# HVSUP_ISOL_Mainboard.net
KiCad netlist of a schematic drawn in Altium Designer
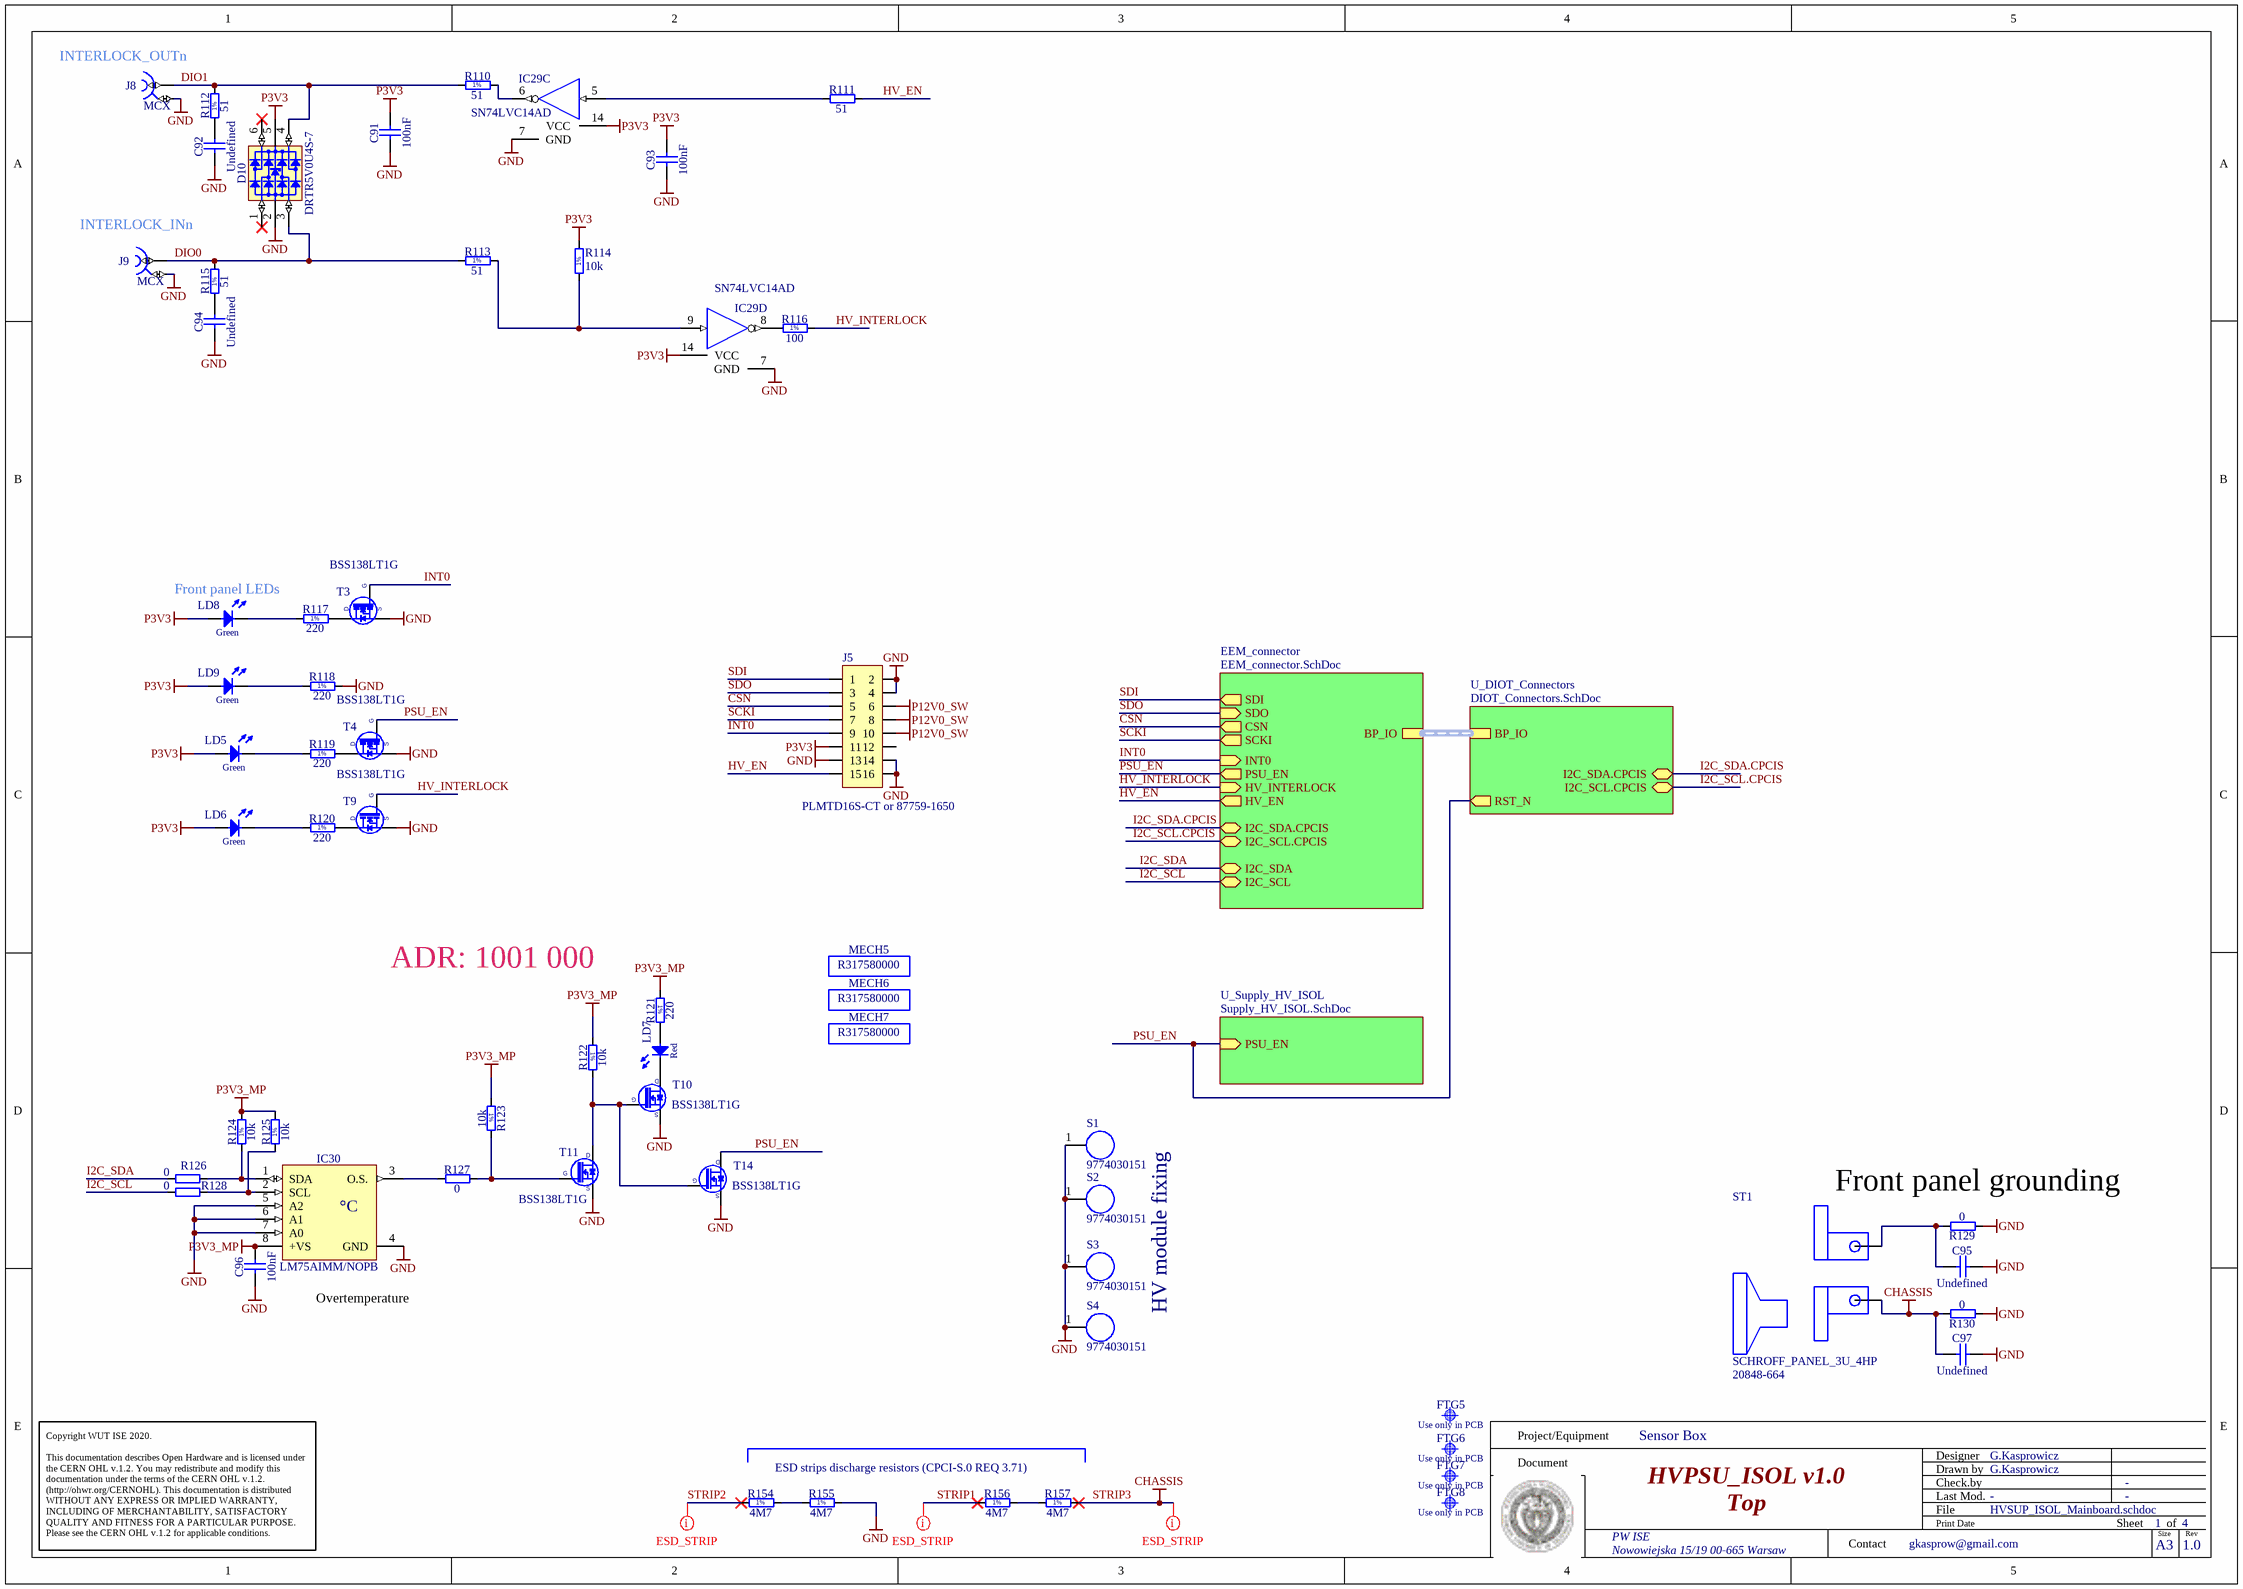
[diagram p0: HVSUP_ISOL_Mainboard.schdoc]

(export (version "E")
  (design (tool "Eeschema 10.0.6"))
  (components
    (comp (ref "C91")
      (value "100nF")
      (footprint "CAPC1005X55N")
      (description "Non-polarised capacitor")
      (fields
        (field (name "PART NUMBER") "CC0402_100NF_16V_10%_X7R")
        (field (name "VOLTAGE") "16V")
        (field (name "AUTHOR") "CERN DEM JLC")
      )
      (libsource (lib "Capacitors") (part "Capacitor - non polarized"))
    )
    (comp (ref "C92")
      (value "Undefined")
      (footprint "CAPC1608X90N")
      (description "Non-polarised capacitor")
      (fields (field (name "PART NUMBER") "CC0603_NO-VALUE") (field (name "AUTHOR") "CERN DEM MR"))
      (libsource (lib "Capacitors") (part "Capacitor - non polarized"))
    )
    (comp (ref "C93")
      (value "100nF")
      (footprint "CAPC1005X55N")
      (description "Non-polarised capacitor")
      (fields
        (field (name "PART NUMBER") "CC0402_100NF_16V_10%_X7R")
        (field (name "VOLTAGE") "16V")
        (field (name "AUTHOR") "CERN DEM JLC")
      )
      (libsource (lib "Capacitors") (part "Capacitor - non polarized"))
    )
    (comp (ref "C94")
      (value "Undefined")
      (footprint "CAPC1608X90N")
      (description "Non-polarised capacitor")
      (fields (field (name "PART NUMBER") "CC0603_NO-VALUE") (field (name "AUTHOR") "CERN DEM MR"))
      (libsource (lib "Capacitors") (part "Capacitor - non polarized"))
    )
    (comp (ref "C95")
      (value "Undefined")
      (footprint "CAPC2012X135N")
      (description "Non-polarised capacitor")
      (fields (field (name "PART NUMBER") "CC0805_NO-VALUE") (field (name "AUTHOR") "CERN DEM JLC"))
      (libsource (lib "Capacitors") (part "Capacitor - non polarized"))
    )
    (comp (ref "C96")
      (value "100nF")
      (footprint "CAPC1005X55N")
      (description "Non-polarised capacitor")
      (fields
        (field (name "PART NUMBER") "CC0402_100NF_16V_10%_X5R")
        (field (name "VOLTAGE") "16V")
        (field (name "AUTHOR") "CERN DEM JLC")
      )
      (libsource (lib "Capacitors") (part "Capacitor - non polarized"))
    )
    (comp (ref "C97")
      (value "Undefined")
      (footprint "CAPC2012X135N")
      (description "Non-polarised capacitor")
      (fields (field (name "PART NUMBER") "CC0805_NO-VALUE") (field (name "AUTHOR") "CERN DEM JLC"))
      (libsource (lib "Capacitors") (part "Capacitor - non polarized"))
    )
    (comp (ref "D10")
      (value "DRTR5V0U4S-7")
      (footprint "SOT65P210X110-6N")
      (description "Integrated Quad Ultra-Low Capacitance ESD Protection")
      (fields (field (name "MANUFACTURER") "DIODES") (field (name "AUTHOR") "GK"))
      (libsource (lib "Diodes") (part "D_TVS_DRTR5V0U4S-7"))
    )
    (comp (ref "FTG5")
      (value "Use only in PCB")
      (footprint "FIDUCIAL_TOP_C100-200")
      (description "Fiducial Target")
      (fields (field (name "PART NUMBER") "FIDUCIAL_TARGET_C100-200") (field (name "AUTHOR") "CERN DEM JLC"))
      (libsource (lib "Eletro-mechanical") (part "Fiducial Target"))
    )
    (comp (ref "FTG6")
      (value "Use only in PCB")
      (footprint "FIDUCIAL_TOP_S100-200")
      (description "Fiducial Target")
      (fields (field (name "PART NUMBER") "FIDUCIAL_TARGET_S100-200") (field (name "AUTHOR") "CERN DEM JLC"))
      (libsource (lib "Eletro-mechanical") (part "Fiducial Target"))
    )
    (comp (ref "FTG7")
      (value "Use only in PCB")
      (footprint "FIDUCIAL_TOP_S100-200")
      (description "Fiducial Target")
      (fields (field (name "PART NUMBER") "FIDUCIAL_TARGET_S100-200") (field (name "AUTHOR") "CERN DEM JLC"))
      (libsource (lib "Eletro-mechanical") (part "Fiducial Target"))
    )
    (comp (ref "FTG8")
      (value "Use only in PCB")
      (footprint "FIDUCIAL_TOP_S100-200")
      (description "Fiducial Target")
      (fields (field (name "PART NUMBER") "FIDUCIAL_TARGET_S100-200") (field (name "AUTHOR") "CERN DEM JLC"))
      (libsource (lib "Eletro-mechanical") (part "Fiducial Target"))
    )
    (comp (ref "IC29")
      (value "SN74LVC14AD")
      (footprint "SOIC127P600X175-14N")
      (description "Hex Schmitt-Trigger Inverter")
      (fields (field (name "MANUFACTURER") "TEXAS INSTRUMENTS") (field (name "AUTHOR") "CERN DEM JMW"))
      (libsource (lib "ICs And Semiconductors") (part "7414"))
    )
    (comp (ref "IC30")
      (value "LM75AIMM/NOPB")
      (footprint "SOP65P490X109-8N")
      (description "Digital Temperature Sensor and Thermal Watchdog with Two-Wire Interface")
      (fields (field (name "MANUFACTURER") "TEXAS INSTRUMENTS") (field (name "AUTHOR") "CERN DEM JLC"))
      (libsource (lib "ICs And Semiconductors") (part "LM75"))
    )
    (comp (ref "J5")
      (value "PLMTD16S-CT or 87759-1650")
      (footprint "87759-1650")
      (description "2mm  dual row rheader (Maritex)")
      (fields (field (name "MANUFACTURER") "Molex") (field (name "MANUFACTURER PART NUMBER") "87759-1650"))
      (libsource (lib "LIBRARY_SCH") (part "CON_2x8 2mm male"))
    )
    (comp (ref "J8")
      (value "MCX")
      (footprint "AMPHENOL_919-383J-51A")
      (fields
        (field (name "PART NUMBER") "AMPHENOL_919-383J-51A")
        (field (name "MANUFACTURER") "AMPHENOL")
        (field (name "MANUFACTURER PART NUMBER") "919-383J-51A")
        (field (name "AUTHOR") "CERN DEM BC")
      )
      (libsource (lib "Connectors") (part "Coax_1Female_1Shield"))
    )
    (comp (ref "J9")
      (value "MCX")
      (footprint "AMPHENOL_919-383J-51A")
      (fields
        (field (name "PART NUMBER") "AMPHENOL_919-383J-51A")
        (field (name "MANUFACTURER") "AMPHENOL")
        (field (name "MANUFACTURER PART NUMBER") "919-383J-51A")
        (field (name "AUTHOR") "CERN DEM BC")
      )
      (libsource (lib "Connectors") (part "Coax_1Female_1Shield"))
    )
    (comp (ref "LD5")
      (value "Green")
      (footprint "LED_DIALIGHT_555-230")
      (description "LED Green 1C 2A")
      (fields
        (field (name "PART NUMBER") "LED_DIALIGHT_555-2301F")
        (field (name "MANUFACTURER") "DIALIGHT")
        (field (name "AUTHOR") "CERN DEM JMW")
      )
      (libsource (lib "ICs And Semiconductors") (part "LED Green 1C 2A"))
    )
    (comp (ref "LD6")
      (value "Green")
      (footprint "LED_DIALIGHT_555-230")
      (description "LED Green 1C 2A")
      (fields
        (field (name "PART NUMBER") "LED_DIALIGHT_555-2301F")
        (field (name "MANUFACTURER") "DIALIGHT")
        (field (name "AUTHOR") "CERN DEM JMW")
      )
      (libsource (lib "ICs And Semiconductors") (part "LED Green 1C 2A"))
    )
    (comp (ref "LD7")
      (value "Red")
      (footprint "LED_DIALIGHT_555-200")
      (description "LED Red 1C 2A")
      (fields
        (field (name "PART NUMBER") "LED_DIALIGHT_555-2001F")
        (field (name "MANUFACTURER") "DIALIGHT")
        (field (name "AUTHOR") "CERN DEM JMW")
      )
      (libsource (lib "ICs And Semiconductors") (part "LED Red 1C 2A"))
    )
    (comp (ref "LD8")
      (value "Green")
      (footprint "LED_DIALIGHT_555-230")
      (description "LED Green 1C 2A")
      (fields
        (field (name "PART NUMBER") "LED_DIALIGHT_555-2301F")
        (field (name "MANUFACTURER") "DIALIGHT")
        (field (name "AUTHOR") "CERN DEM JMW")
      )
      (libsource (lib "ICs And Semiconductors") (part "LED Green 1C 2A"))
    )
    (comp (ref "LD9")
      (value "Green")
      (footprint "LED_DIALIGHT_555-230")
      (description "LED Green 1C 2A")
      (fields
        (field (name "PART NUMBER") "LED_DIALIGHT_555-2301F")
        (field (name "MANUFACTURER") "DIALIGHT")
        (field (name "AUTHOR") "CERN DEM JMW")
      )
      (libsource (lib "ICs And Semiconductors") (part "LED Green 1C 2A"))
    )
    (comp (ref "MECH5")
      (value "R317580000")
      (footprint "GENERIC_MECH")
      (description "SHV connector")
      (fields (field (name "MANUFACTURER") "Radiall") (field (name "AUTHOR") "GK"))
      (libsource (lib "Mechanical") (part "Generic_mechanical"))
    )
    (comp (ref "MECH6")
      (value "R317580000")
      (footprint "GENERIC_MECH")
      (description "SHV connector")
      (fields (field (name "MANUFACTURER") "Radiall") (field (name "AUTHOR") "GK"))
      (libsource (lib "Mechanical") (part "Generic_mechanical"))
    )
    (comp (ref "MECH7")
      (value "R317580000")
      (footprint "GENERIC_MECH")
      (description "SHV connector")
      (fields (field (name "MANUFACTURER") "Radiall") (field (name "AUTHOR") "GK"))
      (libsource (lib "Mechanical") (part "Generic_mechanical"))
    )
    (comp (ref "R110")
      (value "51")
      (footprint "RESC1005X40N")
      (description "Resistor - 1%")
      (fields
        (field (name "PART NUMBER") "R0402_51R_1%_0.0625W_100PPM")
        (field (name "POWER") "0.0625W")
        (field (name "AUTHOR") "CERN DEM JLC")
      )
      (libsource (lib "Resistors") (part "Resistor - 1%"))
    )
    (comp (ref "R111")
      (value "51")
      (footprint "RESC1005X40N")
      (description "Resistor - 1%")
      (fields
        (field (name "PART NUMBER") "R0402_51R_1%_0.0625W_100PPM")
        (field (name "POWER") "0.0625W")
        (field (name "AUTHOR") "CERN DEM JLC")
      )
      (libsource (lib "Resistors") (part "Resistor - 1%"))
    )
    (comp (ref "R112")
      (value "51")
      (footprint "RESC1005X40N")
      (description "Resistor - 1%")
      (fields
        (field (name "PART NUMBER") "R0402_51R_1%_0.0625W_100PPM")
        (field (name "POWER") "0.0625W")
        (field (name "AUTHOR") "CERN DEM JLC")
      )
      (libsource (lib "Resistors") (part "Resistor - 1%"))
    )
    (comp (ref "R113")
      (value "51")
      (footprint "RESC1005X40N")
      (description "Resistor - 1%")
      (fields
        (field (name "PART NUMBER") "R0402_51R_1%_0.0625W_100PPM")
        (field (name "POWER") "0.0625W")
        (field (name "AUTHOR") "CERN DEM JLC")
      )
      (libsource (lib "Resistors") (part "Resistor - 1%"))
    )
    (comp (ref "R114")
      (value "10k")
      (footprint "RESC1005X40N")
      (description "Resistor - 1%")
      (fields
        (field (name "PART NUMBER") "R0402_10K_1%_0.0625W_100PPM")
        (field (name "POWER") "0.0625W")
        (field (name "AUTHOR") "CERN DEM JLC")
      )
      (libsource (lib "Resistors") (part "Resistor - 1%"))
    )
    (comp (ref "R115")
      (value "51")
      (footprint "RESC1005X40N")
      (description "Resistor - 1%")
      (fields
        (field (name "PART NUMBER") "R0402_51R_1%_0.0625W_100PPM")
        (field (name "POWER") "0.0625W")
        (field (name "AUTHOR") "CERN DEM JLC")
      )
      (libsource (lib "Resistors") (part "Resistor - 1%"))
    )
    (comp (ref "R116")
      (value "100")
      (footprint "RESC1005X40N")
      (description "Resistor - 1%")
      (fields
        (field (name "PART NUMBER") "R0402_100R_1%_0.0625W_100PPM")
        (field (name "POWER") "0.0625W")
        (field (name "AUTHOR") "CERN DEM JLC")
      )
      (libsource (lib "Resistors") (part "Resistor - 1%"))
    )
    (comp (ref "R117")
      (value "220")
      (footprint "RESC1608X55N")
      (description "Resistor - 1%")
      (fields
        (field (name "PART NUMBER") "R0603_220R_1%_0.1W_100PPM")
        (field (name "POWER") "0.1W")
        (field (name "AUTHOR") "CERN DEM JLC")
      )
      (libsource (lib "Resistors") (part "Resistor - 1%"))
    )
    (comp (ref "R118")
      (value "220")
      (footprint "RESC1608X55N")
      (description "Resistor - 1%")
      (fields
        (field (name "PART NUMBER") "R0603_220R_1%_0.1W_100PPM")
        (field (name "POWER") "0.1W")
        (field (name "AUTHOR") "CERN DEM JLC")
      )
      (libsource (lib "Resistors") (part "Resistor - 1%"))
    )
    (comp (ref "R119")
      (value "220")
      (footprint "RESC1608X55N")
      (description "Resistor - 1%")
      (fields
        (field (name "PART NUMBER") "R0603_220R_1%_0.1W_100PPM")
        (field (name "POWER") "0.1W")
        (field (name "AUTHOR") "CERN DEM JLC")
      )
      (libsource (lib "Resistors") (part "Resistor - 1%"))
    )
    (comp (ref "R120")
      (value "220")
      (footprint "RESC1608X55N")
      (description "Resistor - 1%")
      (fields
        (field (name "PART NUMBER") "R0603_220R_1%_0.1W_100PPM")
        (field (name "POWER") "0.1W")
        (field (name "AUTHOR") "CERN DEM JLC")
      )
      (libsource (lib "Resistors") (part "Resistor - 1%"))
    )
    (comp (ref "R121")
      (value "220")
      (footprint "RESC1608X55N")
      (description "Resistor - 1%")
      (fields
        (field (name "PART NUMBER") "R0603_220R_1%_0.1W_100PPM")
        (field (name "POWER") "0.1W")
        (field (name "AUTHOR") "CERN DEM JLC")
      )
      (libsource (lib "Resistors") (part "Resistor - 1%"))
    )
    (comp (ref "R122")
      (value "10k")
      (footprint "RESC1005X40N")
      (description "Resistor - 1%")
      (fields
        (field (name "PART NUMBER") "R0402_10K_1%_0.0625W_100PPM")
        (field (name "POWER") "0.0625W")
        (field (name "AUTHOR") "CERN DEM JLC")
      )
      (libsource (lib "Resistors") (part "Resistor - 1%"))
    )
    (comp (ref "R123")
      (value "10k")
      (footprint "RESC1005X40N")
      (description "Resistor - 1%")
      (fields
        (field (name "PART NUMBER") "R0402_10K_1%_0.0625W_100PPM")
        (field (name "POWER") "0.0625W")
        (field (name "AUTHOR") "CERN DEM JLC")
      )
      (libsource (lib "Resistors") (part "Resistor - 1%"))
    )
    (comp (ref "R124")
      (value "10k")
      (footprint "RESC1005X40N")
      (description "Resistor - 1%")
      (fields
        (field (name "PART NUMBER") "R0402_10K_1%_0.0625W_100PPM")
        (field (name "POWER") "0.0625W")
        (field (name "AUTHOR") "CERN DEM JLC")
      )
      (libsource (lib "Resistors") (part "Resistor - 1%"))
    )
    (comp (ref "R125")
      (value "10k")
      (footprint "RESC1005X40N")
      (description "Resistor - 1%")
      (fields
        (field (name "PART NUMBER") "R0402_10K_1%_0.0625W_100PPM")
        (field (name "POWER") "0.0625W")
        (field (name "AUTHOR") "CERN DEM JLC")
      )
      (libsource (lib "Resistors") (part "Resistor - 1%"))
    )
    (comp (ref "R126")
      (value "0")
      (footprint "RESC1005X40N")
      (description "Resistor")
      (fields
        (field (name "PART NUMBER") "R0402_0R_JUMPER")
        (field (name "MANUFACTURER") "GENERIC")
        (field (name "AUTHOR") "CERN DEM JLC")
      )
      (libsource (lib "Resistors") (part "Resistor"))
    )
    (comp (ref "R127")
      (value "0")
      (footprint "RESC1005X40N")
      (description "Resistor")
      (fields
        (field (name "PART NUMBER") "R0402_0R_JUMPER")
        (field (name "MANUFACTURER") "GENERIC")
        (field (name "AUTHOR") "CERN DEM JLC")
      )
      (libsource (lib "Resistors") (part "Resistor"))
    )
    (comp (ref "R128")
      (value "0")
      (footprint "RESC1005X40N")
      (description "Resistor")
      (fields
        (field (name "PART NUMBER") "R0402_0R_JUMPER")
        (field (name "MANUFACTURER") "GENERIC")
        (field (name "AUTHOR") "CERN DEM JLC")
      )
      (libsource (lib "Resistors") (part "Resistor"))
    )
    (comp (ref "R129")
      (value "0")
      (footprint "RESC1608X55N")
      (description "Resistor")
      (fields
        (field (name "PART NUMBER") "R0603_0R_JUMPER")
        (field (name "MANUFACTURER") "GENERIC")
        (field (name "AUTHOR") "CERN DEM JLC")
      )
      (libsource (lib "Resistors") (part "Resistor"))
    )
    (comp (ref "R130")
      (value "0")
      (footprint "RESC1608X55N")
      (description "Resistor")
      (fields
        (field (name "PART NUMBER") "R0603_0R_JUMPER")
        (field (name "MANUFACTURER") "GENERIC")
        (field (name "AUTHOR") "CERN DEM JLC")
      )
      (libsource (lib "Resistors") (part "Resistor"))
    )
    (comp (ref "R154")
      (value "4M7")
      (footprint "RESC2113X55N")
      (description "Resistor - 1%")
      (fields
        (field (name "PART NUMBER") "R0805_4M7_1%_0.125W_100PPM_VISHAY_CRCW e3")
        (field (name "POWER") "0.125W")
        (field (name "AUTHOR") "CERN DEM BR")
      )
      (libsource (lib "Resistors") (part "Resistor - 1%"))
    )
    (comp (ref "R155")
      (value "4M7")
      (footprint "RESC2113X55N")
      (description "Resistor - 1%")
      (fields
        (field (name "PART NUMBER") "R0805_4M7_1%_0.125W_100PPM_VISHAY_CRCW e3")
        (field (name "POWER") "0.125W")
        (field (name "AUTHOR") "CERN DEM BR")
      )
      (libsource (lib "Resistors") (part "Resistor - 1%"))
    )
    (comp (ref "R156")
      (value "4M7")
      (footprint "RESC2113X55N")
      (description "Resistor - 1%")
      (fields
        (field (name "PART NUMBER") "R0805_4M7_1%_0.125W_100PPM_VISHAY_CRCW e3")
        (field (name "POWER") "0.125W")
        (field (name "AUTHOR") "CERN DEM BR")
      )
      (libsource (lib "Resistors") (part "Resistor - 1%"))
    )
    (comp (ref "R157")
      (value "4M7")
      (footprint "RESC2113X55N")
      (description "Resistor - 1%")
      (fields
        (field (name "PART NUMBER") "R0805_4M7_1%_0.125W_100PPM_VISHAY_CRCW e3")
        (field (name "POWER") "0.125W")
        (field (name "AUTHOR") "CERN DEM BR")
      )
      (libsource (lib "Resistors") (part "Resistor - 1%"))
    )
    (comp (ref "S1")
      (value "9774030151")
      (footprint "9774030151")
      (description "WA-SMSI SMD Steel Spacer with internal Thread")
      (fields (field (name "MANUFACTURER") "Wurth Elektronik") (field (name "CREATED BY") "Baojun Chen"))
      (libsource (lib "Altium_SMSI_SMT_STEEL_SPACER_M2_5_THREAD_INTERNAL_rev15a") (part "WA-SMSI,  9774030151"))
    )
    (comp (ref "S2")
      (value "9774030151")
      (footprint "9774030151")
      (description "WA-SMSI SMD Steel Spacer with internal Thread")
      (fields (field (name "MANUFACTURER") "Wurth Elektronik") (field (name "CREATED BY") "Baojun Chen"))
      (libsource (lib "Altium_SMSI_SMT_STEEL_SPACER_M2_5_THREAD_INTERNAL_rev15a") (part "WA-SMSI,  9774030151"))
    )
    (comp (ref "S3")
      (value "9774030151")
      (footprint "9774030151")
      (description "WA-SMSI SMD Steel Spacer with internal Thread")
      (fields (field (name "MANUFACTURER") "Wurth Elektronik") (field (name "CREATED BY") "Baojun Chen"))
      (libsource (lib "Altium_SMSI_SMT_STEEL_SPACER_M2_5_THREAD_INTERNAL_rev15a") (part "WA-SMSI,  9774030151"))
    )
    (comp (ref "S4")
      (value "9774030151")
      (footprint "9774030151")
      (description "WA-SMSI SMD Steel Spacer with internal Thread")
      (fields (field (name "MANUFACTURER") "Wurth Elektronik") (field (name "CREATED BY") "Baojun Chen"))
      (libsource (lib "Altium_SMSI_SMT_STEEL_SPACER_M2_5_THREAD_INTERNAL_rev15a") (part "WA-SMSI,  9774030151"))
    )
    (comp (ref "ST1")
      (value "SCHROFF_PANEL_3U_4HP")
      (footprint "SCHROFF_PANEL_3HP_4U")
      (description "Schroff 3HP 4U EUROCARD Panel Kit")
      (fields
        (field (name "MANUFACTURER") "Schroff")
        (field (name "MANUFACTURER PART NUMBER") "20818-017")
        (field (name "MANUFACTURER PART NUMBER 2") "20848-664")
      )
      (libsource (lib "Mechanical") (part "SCHROFF_PANEL_3U_4HP"))
    )
    (comp (ref "T3")
      (value "BSS138LT1G")
      (footprint "SOT95P240X110-3N")
      (description "N-CHANNEL MOSFET WITH DIODE")
      (fields (field (name "MANUFACTURER") "ON SEMICONDUCTOR") (field (name "AUTHOR") "CERN DEM JLC"))
      (libsource (lib "") (part "N-MOSFET-D 1G 2S 3D_2"))
    )
    (comp (ref "T4")
      (value "BSS138LT1G")
      (footprint "SOT95P240X110-3N")
      (description "N-CHANNEL MOSFET WITH DIODE")
      (fields (field (name "MANUFACTURER") "ON SEMICONDUCTOR") (field (name "AUTHOR") "CERN DEM JLC"))
      (libsource (lib "") (part "N-MOSFET-D 1G 2S 3D_2"))
    )
    (comp (ref "T9")
      (value "BSS138LT1G")
      (footprint "SOT95P240X110-3N")
      (description "N-CHANNEL MOSFET WITH DIODE")
      (fields (field (name "MANUFACTURER") "ON SEMICONDUCTOR") (field (name "AUTHOR") "CERN DEM JLC"))
      (libsource (lib "") (part "N-MOSFET-D 1G 2S 3D_2"))
    )
    (comp (ref "T10")
      (value "BSS138LT1G")
      (footprint "SOT95P240X110-3N")
      (description "N-CHANNEL MOSFET WITH DIODE")
      (fields (field (name "MANUFACTURER") "ON SEMICONDUCTOR") (field (name "AUTHOR") "CERN DEM JLC"))
      (libsource (lib "ICs And Semiconductors") (part "N-MOSFET-D 1G 2S 3D"))
    )
    (comp (ref "T11")
      (value "BSS138LT1G")
      (footprint "SOT95P240X110-3N")
      (description "N-CHANNEL MOSFET WITH DIODE")
      (fields (field (name "MANUFACTURER") "ON SEMICONDUCTOR") (field (name "AUTHOR") "CERN DEM JLC"))
      (libsource (lib "") (part "N-MOSFET-D 1G 2S 3D_1"))
    )
    (comp (ref "T14")
      (value "BSS138LT1G")
      (footprint "SOT95P240X110-3N")
      (description "N-CHANNEL MOSFET WITH DIODE")
      (fields (field (name "MANUFACTURER") "ON SEMICONDUCTOR") (field (name "AUTHOR") "CERN DEM JLC"))
      (libsource (lib "ICs And Semiconductors") (part "N-MOSFET-D 1G 2S 3D"))
    )
  )
  (nets
    (net (code "2") (name "/CSN") (class "Default")
      (node (ref "J5") (pin "5") (pinfunction "5_5") (pintype "passive"))
    )
    (net (code "3") (name "/DIO0") (class "Default")
      (node (ref "D10") (pin "3") (pinfunction "I/O2_3") (pintype "bidirectional"))
      (node (ref "J9") (pin "1") (pinfunction "1_1") (pintype "bidirectional"))
      (node (ref "R113") (pin "1") (pinfunction "1_1") (pintype "passive"))
      (node (ref "R115") (pin "2") (pinfunction "2_2") (pintype "passive"))
    )
    (net (code "4") (name "/DIO1") (class "Default")
      (node (ref "D10") (pin "4") (pinfunction "I/O3_4") (pintype "bidirectional"))
      (node (ref "J8") (pin "1") (pinfunction "1_1") (pintype "bidirectional"))
      (node (ref "R110") (pin "1") (pinfunction "1_1") (pintype "passive"))
      (node (ref "R112") (pin "2") (pinfunction "2_2") (pintype "passive"))
    )
    (net (code "5") (name "/HV_EN") (class "Default")
      (node (ref "J5") (pin "15") (pinfunction "15_15") (pintype "passive"))
      (node (ref "R111") (pin "2") (pinfunction "2_2") (pintype "passive"))
    )
    (net (code "6") (name "/HV_INTERLOCK") (class "Default")
      (node (ref "R116") (pin "2") (pinfunction "2_2") (pintype "passive"))
      (node (ref "T9") (pin "1") (pinfunction "G_1") (pintype "passive"))
    )
    (net (code "7") (name "/I2C_SCL") (class "Default")
      (node (ref "R128") (pin "1") (pinfunction "1_1") (pintype "passive"))
    )
    (net (code "9") (name "/I2C_SDA") (class "Default")
      (node (ref "R126") (pin "1") (pinfunction "1_1") (pintype "passive"))
    )
    (net (code "11") (name "/INT0") (class "Default")
      (node (ref "J5") (pin "9") (pinfunction "9_9") (pintype "passive"))
      (node (ref "T3") (pin "1") (pinfunction "G_1") (pintype "passive"))
    )
    (net (code "12") (name "/PSU_EN") (class "Default")
      (node (ref "T14") (pin "3") (pinfunction "D_3") (pintype "passive"))
      (node (ref "T4") (pin "1") (pinfunction "G_1") (pintype "passive"))
    )
    (net (code "13") (name "/SCKI") (class "Default")
      (node (ref "J5") (pin "7") (pinfunction "7_7") (pintype "passive"))
    )
    (net (code "14") (name "/SDI") (class "Default")
      (node (ref "J5") (pin "1") (pinfunction "1_1") (pintype "passive"))
    )
    (net (code "15") (name "/SDO") (class "Default")
      (node (ref "J5") (pin "3") (pinfunction "3_3") (pintype "passive"))
    )
    (net (code "16") (name "/STRIP1") (class "Default")
      (node (ref "R156") (pin "1") (pinfunction "1_1") (pintype "passive+no_connect"))
    )
    (net (code "17") (name "/STRIP2") (class "Default")
      (node (ref "R154") (pin "1") (pinfunction "1_1") (pintype "passive+no_connect"))
    )
    (net (code "18") (name "CHASSIS") (class "Default")
      (node (ref "C97") (pin "1") (pinfunction "1_1") (pintype "passive"))
      (node (ref "R130") (pin "2") (pinfunction "2_2") (pintype "passive"))
      (node (ref "R157") (pin "2") (pinfunction "2_2") (pintype "passive"))
      (node (ref "ST1") (pin "0") (pinfunction "0_0") (pintype "passive"))
    )
    (net (code "19") (name "GND") (class "Default")
      (node (ref "C91") (pin "1") (pinfunction "1_1") (pintype "passive"))
      (node (ref "C92") (pin "1") (pinfunction "1_1") (pintype "passive"))
      (node (ref "C93") (pin "1") (pinfunction "1_1") (pintype "passive"))
      (node (ref "C94") (pin "1") (pinfunction "1_1") (pintype "passive"))
      (node (ref "C95") (pin "2") (pinfunction "2_2") (pintype "passive"))
      (node (ref "C96") (pin "1") (pinfunction "1_1") (pintype "passive"))
      (node (ref "C97") (pin "2") (pinfunction "2_2") (pintype "passive"))
      (node (ref "D10") (pin "2") (pinfunction "GND_2") (pintype "power_in"))
      (node (ref "IC29") (pin "7") (pinfunction "GND_7") (pintype "power_in"))
      (node (ref "IC30") (pin "4") (pinfunction "GND_4") (pintype "power_in"))
      (node (ref "IC30") (pin "5") (pinfunction "A2_5") (pintype "input"))
      (node (ref "IC30") (pin "6") (pinfunction "A1_6") (pintype "input"))
      (node (ref "IC30") (pin "7") (pinfunction "A0_7") (pintype "input"))
      (node (ref "J5") (pin "13") (pinfunction "13_13") (pintype "passive"))
      (node (ref "J5") (pin "14") (pinfunction "14_14") (pintype "passive"))
      (node (ref "J5") (pin "16") (pinfunction "16_16") (pintype "passive"))
      (node (ref "J5") (pin "2") (pinfunction "2_2") (pintype "passive"))
      (node (ref "J5") (pin "4") (pinfunction "4_4") (pintype "passive"))
      (node (ref "J8") (pin "2") (pinfunction "2_2") (pintype "bidirectional"))
      (node (ref "J9") (pin "2") (pinfunction "2_2") (pintype "bidirectional"))
      (node (ref "R118") (pin "2") (pinfunction "2_2") (pintype "passive"))
      (node (ref "R129") (pin "1") (pinfunction "1_1") (pintype "passive"))
      (node (ref "R130") (pin "1") (pinfunction "1_1") (pintype "passive"))
      (node (ref "R155") (pin "2") (pinfunction "2_2") (pintype "passive"))
      (node (ref "S1") (pin "1") (pinfunction "1_1") (pintype "passive"))
      (node (ref "S2") (pin "1") (pinfunction "1_1") (pintype "passive"))
      (node (ref "S3") (pin "1") (pinfunction "1_1") (pintype "passive"))
      (node (ref "S4") (pin "1") (pinfunction "1_1") (pintype "passive"))
      (node (ref "T10") (pin "2") (pinfunction "S_2") (pintype "passive"))
      (node (ref "T11") (pin "2") (pinfunction "S_2") (pintype "passive"))
      (node (ref "T14") (pin "2") (pinfunction "S_2") (pintype "passive"))
      (node (ref "T3") (pin "2") (pinfunction "S_2") (pintype "passive"))
      (node (ref "T4") (pin "2") (pinfunction "S_2") (pintype "passive"))
      (node (ref "T9") (pin "2") (pinfunction "S_2") (pintype "passive"))
    )
    (net (code "20") (name "Net-(C92-Pad2)") (class "Default")
      (node (ref "C92") (pin "2") (pinfunction "2_2") (pintype "passive"))
      (node (ref "R112") (pin "1") (pinfunction "1_1") (pintype "passive"))
    )
    (net (code "21") (name "Net-(C94-Pad2)") (class "Default")
      (node (ref "C94") (pin "2") (pinfunction "2_2") (pintype "passive"))
      (node (ref "R115") (pin "1") (pinfunction "1_1") (pintype "passive"))
    )
    (net (code "22") (name "Net-(C95-Pad1)") (class "Default")
      (node (ref "C95") (pin "1") (pinfunction "1_1") (pintype "passive"))
      (node (ref "R129") (pin "2") (pinfunction "2_2") (pintype "passive"))
      (node (ref "ST1") (pin "1") (pinfunction "1_1") (pintype "passive"))
    )
    (net (code "23") (name "Net-(IC29C-IN)") (class "Default")
      (node (ref "IC29") (pin "5") (pinfunction "IN_5") (pintype "input"))
      (node (ref "R111") (pin "1") (pinfunction "1_1") (pintype "passive"))
    )
    (net (code "24") (name "Net-(IC29C-OUT)") (class "Default")
      (node (ref "IC29") (pin "6") (pinfunction "OUT_6") (pintype "output"))
      (node (ref "R110") (pin "2") (pinfunction "2_2") (pintype "passive"))
    )
    (net (code "25") (name "Net-(IC29D-IN)") (class "Default")
      (node (ref "IC29") (pin "9") (pinfunction "IN_9") (pintype "input"))
      (node (ref "R113") (pin "2") (pinfunction "2_2") (pintype "passive"))
      (node (ref "R114") (pin "1") (pinfunction "1_1") (pintype "passive"))
    )
    (net (code "26") (name "Net-(IC29D-OUT)") (class "Default")
      (node (ref "IC29") (pin "8") (pinfunction "OUT_8") (pintype "output"))
      (node (ref "R116") (pin "1") (pinfunction "1_1") (pintype "passive"))
    )
    (net (code "27") (name "Net-(IC30-O.S.)") (class "Default")
      (node (ref "IC30") (pin "3") (pinfunction "O.S._3") (pintype "output"))
      (node (ref "R127") (pin "1") (pinfunction "1_1") (pintype "passive"))
    )
    (net (code "28") (name "Net-(IC30-SCL)") (class "Default")
      (node (ref "IC30") (pin "2") (pinfunction "SCL_2") (pintype "input"))
      (node (ref "R125") (pin "1") (pinfunction "1_1") (pintype "passive"))
      (node (ref "R128") (pin "2") (pinfunction "2_2") (pintype "passive"))
    )
    (net (code "29") (name "Net-(IC30-SDA)") (class "Default")
      (node (ref "IC30") (pin "1") (pinfunction "SDA_1") (pintype "bidirectional"))
      (node (ref "R124") (pin "1") (pinfunction "1_1") (pintype "passive"))
      (node (ref "R126") (pin "2") (pinfunction "2_2") (pintype "passive"))
    )
    (net (code "30") (name "Net-(LD5-C)") (class "Default")
      (node (ref "LD5") (pin "1") (pinfunction "C_1") (pintype "passive"))
      (node (ref "R119") (pin "1") (pinfunction "1_1") (pintype "passive"))
    )
    (net (code "31") (name "Net-(LD6-C)") (class "Default")
      (node (ref "LD6") (pin "1") (pinfunction "C_1") (pintype "passive"))
      (node (ref "R120") (pin "1") (pinfunction "1_1") (pintype "passive"))
    )
    (net (code "32") (name "Net-(LD7-A)") (class "Default")
      (node (ref "LD7") (pin "2") (pinfunction "A_2") (pintype "passive"))
      (node (ref "R121") (pin "2") (pinfunction "2_2") (pintype "passive"))
    )
    (net (code "33") (name "Net-(LD7-C)") (class "Default")
      (node (ref "LD7") (pin "1") (pinfunction "C_1") (pintype "passive"))
      (node (ref "T10") (pin "3") (pinfunction "D_3") (pintype "passive"))
    )
    (net (code "34") (name "Net-(LD8-C)") (class "Default")
      (node (ref "LD8") (pin "1") (pinfunction "C_1") (pintype "passive"))
      (node (ref "R117") (pin "1") (pinfunction "1_1") (pintype "passive"))
    )
    (net (code "35") (name "Net-(LD9-C)") (class "Default")
      (node (ref "LD9") (pin "1") (pinfunction "C_1") (pintype "passive"))
      (node (ref "R118") (pin "1") (pinfunction "1_1") (pintype "passive"))
    )
    (net (code "36") (name "Net-(R154-Pad2)") (class "Default")
      (node (ref "R154") (pin "2") (pinfunction "2_2") (pintype "passive"))
      (node (ref "R155") (pin "1") (pinfunction "1_1") (pintype "passive"))
    )
    (net (code "37") (name "Net-(R156-Pad2)") (class "Default")
      (node (ref "R156") (pin "2") (pinfunction "2_2") (pintype "passive"))
      (node (ref "R157") (pin "1") (pinfunction "1_1") (pintype "passive"))
    )
    (net (code "38") (name "Net-(T3-D)") (class "Default")
      (node (ref "R117") (pin "2") (pinfunction "2_2") (pintype "passive"))
      (node (ref "T3") (pin "3") (pinfunction "D_3") (pintype "passive"))
    )
    (net (code "39") (name "Net-(T4-D)") (class "Default")
      (node (ref "R119") (pin "2") (pinfunction "2_2") (pintype "passive"))
      (node (ref "T4") (pin "3") (pinfunction "D_3") (pintype "passive"))
    )
    (net (code "40") (name "Net-(T9-D)") (class "Default")
      (node (ref "R120") (pin "2") (pinfunction "2_2") (pintype "passive"))
      (node (ref "T9") (pin "3") (pinfunction "D_3") (pintype "passive"))
    )
    (net (code "41") (name "Net-(T10-G)") (class "Default")
      (node (ref "R122") (pin "2") (pinfunction "2_2") (pintype "passive"))
      (node (ref "T10") (pin "1") (pinfunction "G_1") (pintype "passive"))
      (node (ref "T11") (pin "3") (pinfunction "D_3") (pintype "passive"))
      (node (ref "T14") (pin "1") (pinfunction "G_1") (pintype "passive"))
    )
    (net (code "42") (name "Net-(T11-G)") (class "Default")
      (node (ref "R123") (pin "2") (pinfunction "2_2") (pintype "passive"))
      (node (ref "R127") (pin "2") (pinfunction "2_2") (pintype "passive"))
      (node (ref "T11") (pin "1") (pinfunction "G_1") (pintype "passive"))
    )
    (net (code "43") (name "P3V3") (class "Default")
      (node (ref "C91") (pin "2") (pinfunction "2_2") (pintype "passive"))
      (node (ref "C93") (pin "2") (pinfunction "2_2") (pintype "passive"))
      (node (ref "D10") (pin "5") (pinfunction "VBUS_5") (pintype "power_in"))
      (node (ref "IC29") (pin "14") (pinfunction "VCC_14") (pintype "power_in"))
      (node (ref "J5") (pin "11") (pinfunction "11_11") (pintype "passive"))
      (node (ref "LD5") (pin "2") (pinfunction "A_2") (pintype "passive"))
      (node (ref "LD6") (pin "2") (pinfunction "A_2") (pintype "passive"))
      (node (ref "LD8") (pin "2") (pinfunction "A_2") (pintype "passive"))
      (node (ref "LD9") (pin "2") (pinfunction "A_2") (pintype "passive"))
      (node (ref "R114") (pin "2") (pinfunction "2_2") (pintype "passive"))
    )
    (net (code "44") (name "P3V3_MP") (class "Default")
      (node (ref "C96") (pin "2") (pinfunction "2_2") (pintype "passive"))
      (node (ref "IC30") (pin "8") (pinfunction "+VS_8") (pintype "power_in"))
      (node (ref "R121") (pin "1") (pinfunction "1_1") (pintype "passive"))
      (node (ref "R122") (pin "1") (pinfunction "1_1") (pintype "passive"))
      (node (ref "R123") (pin "1") (pinfunction "1_1") (pintype "passive"))
      (node (ref "R124") (pin "2") (pinfunction "2_2") (pintype "passive"))
      (node (ref "R125") (pin "2") (pinfunction "2_2") (pintype "passive"))
    )
    (net (code "45") (name "P12V0_SW") (class "Default")
      (node (ref "J5") (pin "10") (pinfunction "10_10") (pintype "passive"))
      (node (ref "J5") (pin "6") (pinfunction "6_6") (pintype "passive"))
      (node (ref "J5") (pin "8") (pinfunction "8_8") (pintype "passive"))
    )
    (net (code "46") (name "unconnected-(D10-I{slash}O1-Pad1)") (class "Default")
      (node (ref "D10") (pin "1") (pinfunction "I/O1_1") (pintype "bidirectional+no_connect"))
    )
    (net (code "47") (name "unconnected-(D10-I{slash}O4-Pad6)") (class "Default")
      (node (ref "D10") (pin "6") (pinfunction "I/O4_6") (pintype "bidirectional+no_connect"))
    )
    (net (code "48") (name "unconnected-(J5-Pad12)") (class "Default")
      (node (ref "J5") (pin "12") (pinfunction "12_12") (pintype "passive"))
    )
  )
)
